# EASY_EDA_FILE_SCHEMATIC.net
KiCad netlist of a schematic drawn in EasyEDA
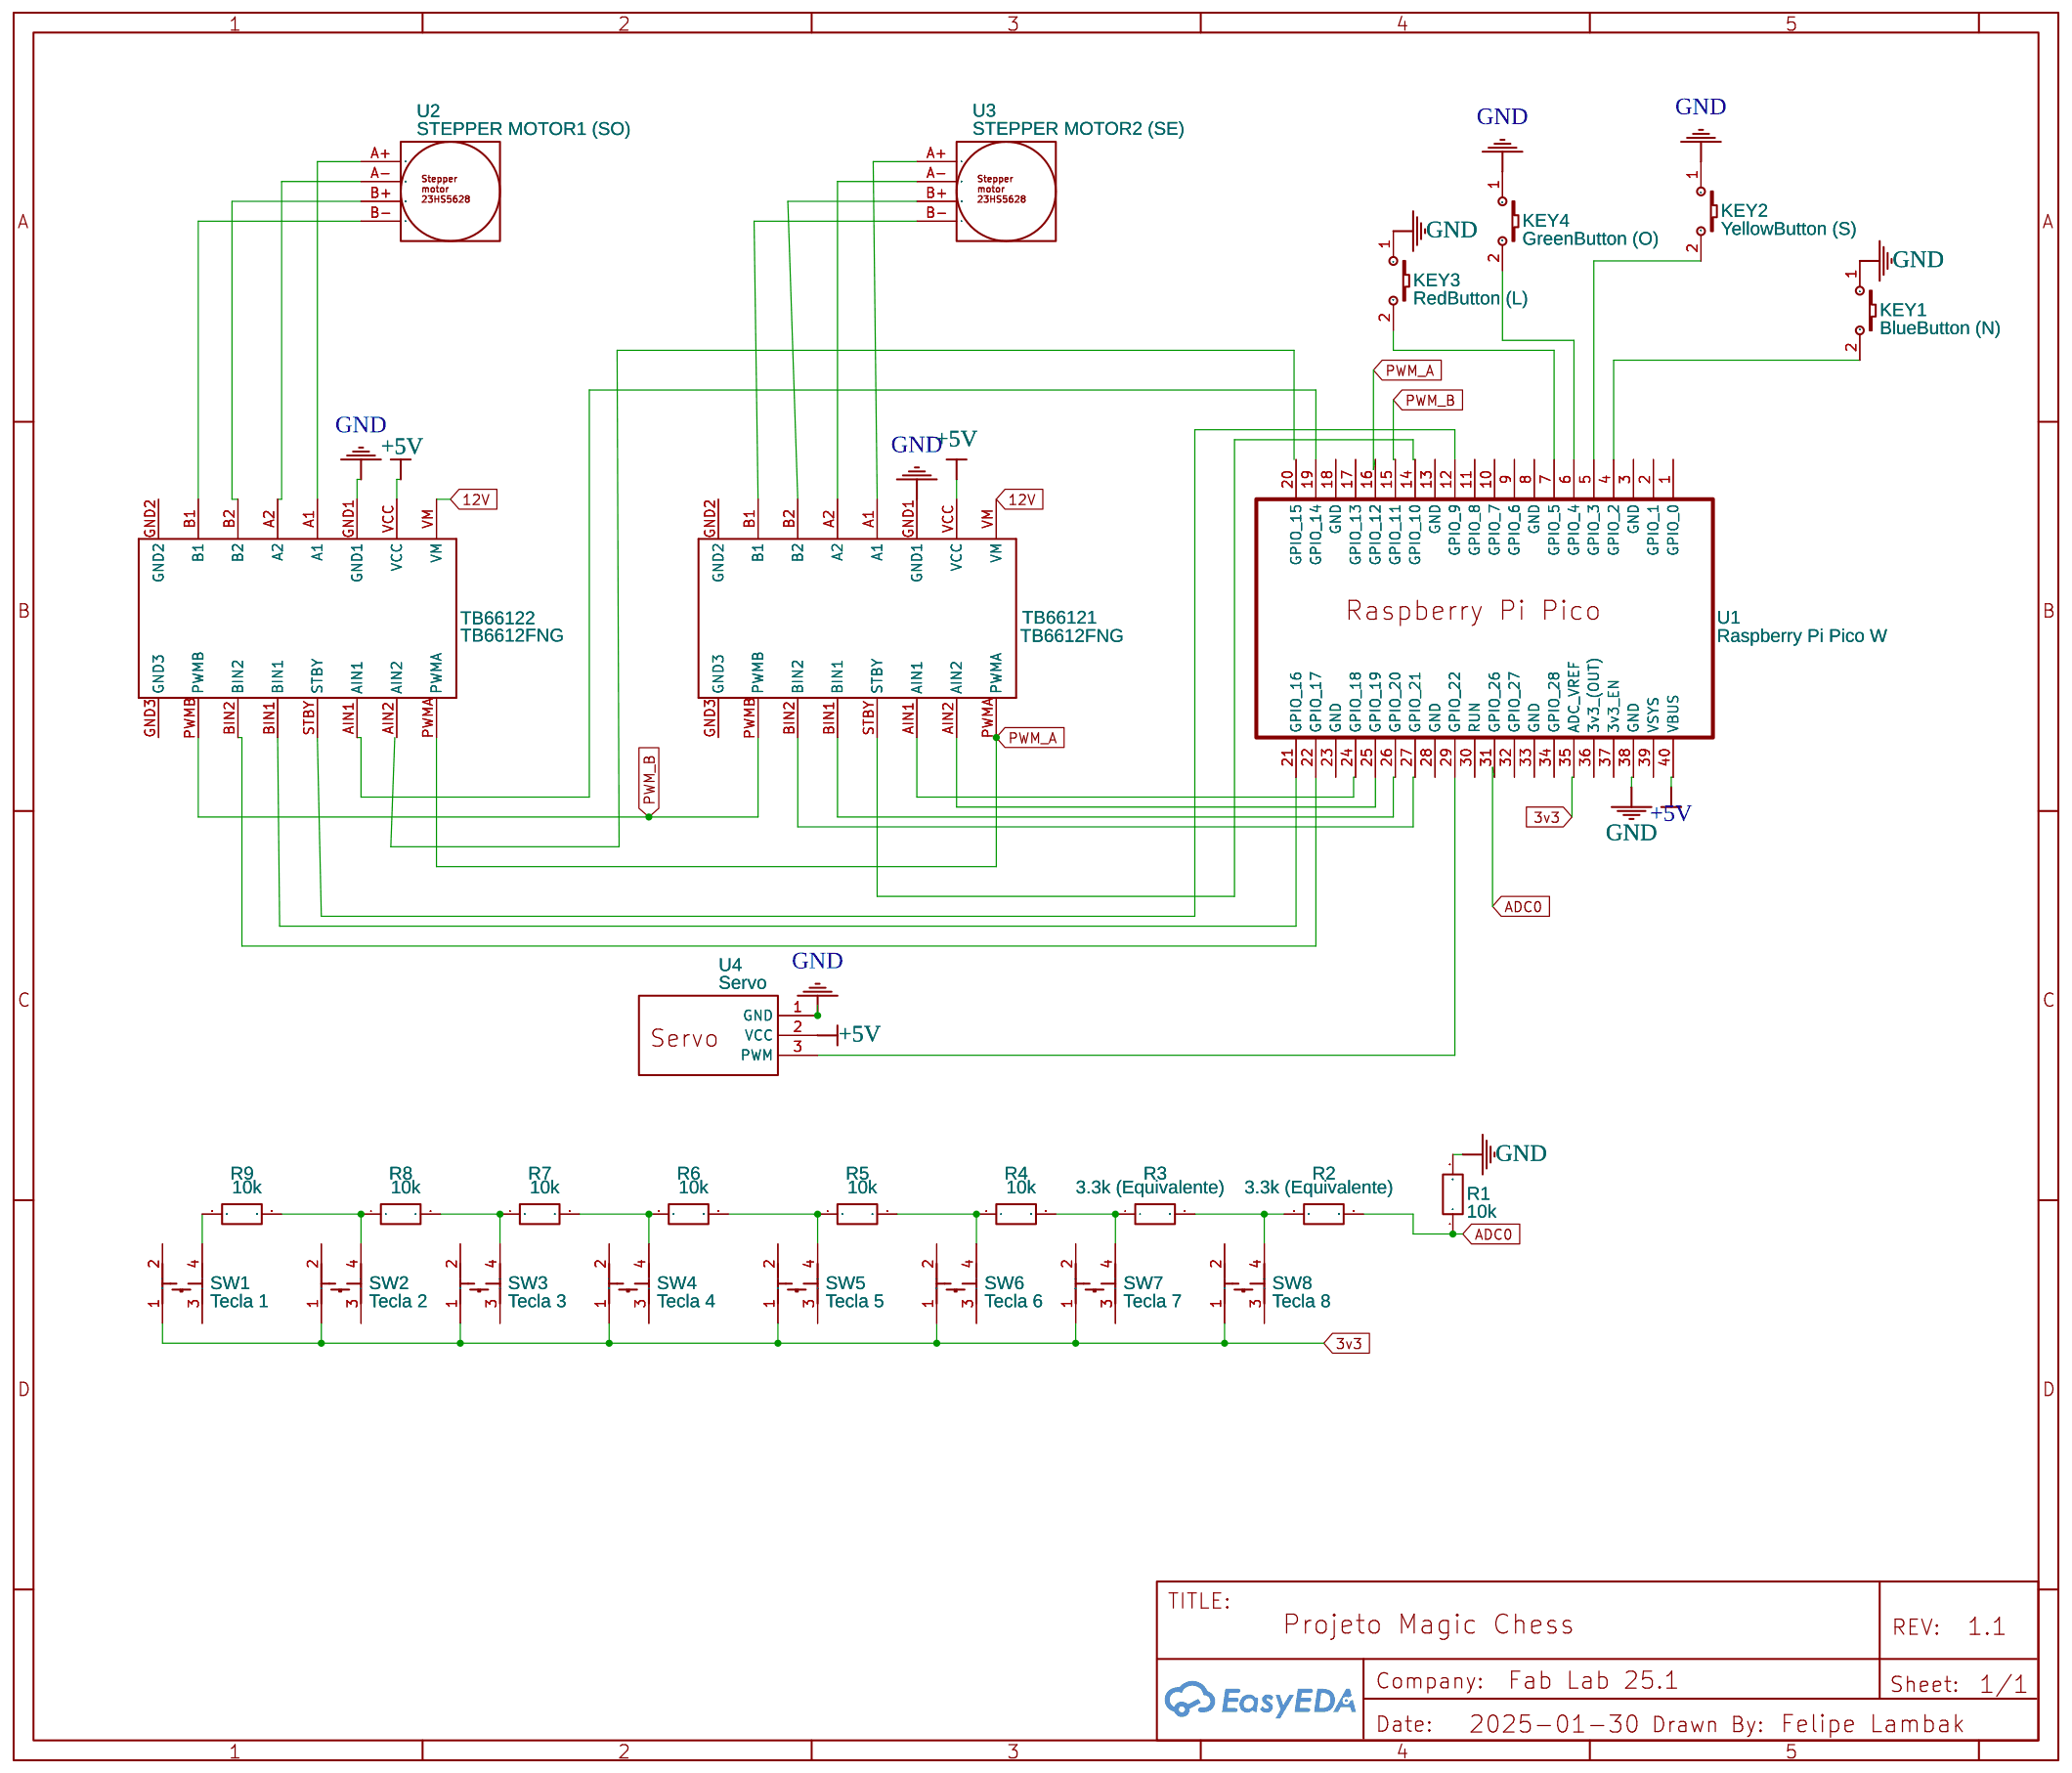
[diagram p0: schematic sheet]

(export (version "E")
  (design (tool "Eeschema 10.0.6"))
  (components
    (comp (ref "KEY1")
      (value "BlueButton (N)")
      (fields (field (name "Manufacturer Part") "K2-1107ST-A4SW-06"))
      (libsource (lib "") (part "K2-3.6×6.1_SMD"))
    )
    (comp (ref "KEY2")
      (value "YellowButton (S)")
      (fields (field (name "Manufacturer Part") "K2-1107ST-A4SW-06"))
      (libsource (lib "") (part "K2-3.6×6.1_SMD"))
    )
    (comp (ref "KEY3")
      (value "RedButton (L)")
      (fields (field (name "Manufacturer Part") "K2-1107ST-A4SW-06"))
      (libsource (lib "") (part "K2-3.6×6.1_SMD"))
    )
    (comp (ref "KEY4")
      (value "GreenButton (O)")
      (fields (field (name "Manufacturer Part") "K2-1107ST-A4SW-06"))
      (libsource (lib "") (part "K2-3.6×6.1_SMD"))
    )
    (comp (ref "R1") (value "10k") (libsource (lib "") (part "R_0603_EU_1")))
    (comp (ref "R2") (value "3.3k (Equivalente)") (libsource (lib "") (part "R_0603_EU")))
    (comp (ref "R3") (value "3.3k (Equivalente)") (libsource (lib "") (part "R_0603_EU")))
    (comp (ref "R4") (value "10k") (libsource (lib "") (part "R_0603_EU")))
    (comp (ref "R5") (value "10k") (libsource (lib "") (part "R_0603_EU")))
    (comp (ref "R6") (value "10k") (libsource (lib "") (part "R_0603_EU")))
    (comp (ref "R7") (value "10k") (libsource (lib "") (part "R_0603_EU")))
    (comp (ref "R8") (value "10k") (libsource (lib "") (part "R_0603_EU")))
    (comp (ref "R9") (value "10k") (libsource (lib "") (part "R_0603_EU")))
    (comp (ref "SW1")
      (value "Tecla 1")
      (fields (field (name "Manufacturer Part") "BUTTON-4X3X2.5"))
      (libsource (lib "") (part "BUTTON-4X3X2.5"))
    )
    (comp (ref "SW2")
      (value "Tecla 2")
      (fields (field (name "Manufacturer Part") "BUTTON-4X3X2.5"))
      (libsource (lib "") (part "BUTTON-4X3X2.5"))
    )
    (comp (ref "SW3")
      (value "Tecla 3")
      (fields (field (name "Manufacturer Part") "BUTTON-4X3X2.5"))
      (libsource (lib "") (part "BUTTON-4X3X2.5"))
    )
    (comp (ref "SW4")
      (value "Tecla 4")
      (fields (field (name "Manufacturer Part") "BUTTON-4X3X2.5"))
      (libsource (lib "") (part "BUTTON-4X3X2.5"))
    )
    (comp (ref "SW5")
      (value "Tecla 5")
      (fields (field (name "Manufacturer Part") "BUTTON-4X3X2.5"))
      (libsource (lib "") (part "BUTTON-4X3X2.5"))
    )
    (comp (ref "SW6")
      (value "Tecla 6")
      (fields (field (name "Manufacturer Part") "BUTTON-4X3X2.5"))
      (libsource (lib "") (part "BUTTON-4X3X2.5"))
    )
    (comp (ref "SW7")
      (value "Tecla 7")
      (fields (field (name "Manufacturer Part") "BUTTON-4X3X2.5"))
      (libsource (lib "") (part "BUTTON-4X3X2.5"))
    )
    (comp (ref "SW8")
      (value "Tecla 8")
      (fields (field (name "Manufacturer Part") "BUTTON-4X3X2.5"))
      (libsource (lib "") (part "BUTTON-4X3X2.5"))
    )
    (comp (ref "TB66121") (value "TB6612FNG") (libsource (lib "") (part "TB6612FNG")))
    (comp (ref "TB66122") (value "TB6612FNG") (libsource (lib "") (part "TB6612FNG")))
    (comp (ref "U1") (value "Raspberry Pi Pico W") (libsource (lib "") (part "Raspberry Pi Pico W")))
    (comp (ref "U2")
      (value "STEPPER MOTOR1 (SO)")
      (fields (field (name "Manufacturer Part") "MOTOR"))
      (libsource (lib "") (part "STEPPER MOTOR"))
    )
    (comp (ref "U3")
      (value "STEPPER MOTOR2 (SE)")
      (fields (field (name "Manufacturer Part") "MOTOR"))
      (libsource (lib "") (part "STEPPER MOTOR"))
    )
    (comp (ref "U4") (value "Servo") (libsource (lib "") (part "Servo")))
  )
  (nets
    (net (code "1") (name "+5V") (class "Default")
      (node (ref "TB66121") (pin "VCC") (pinfunction "VCC_VCC") (pintype "bidirectional"))
      (node (ref "TB66122") (pin "VCC") (pinfunction "VCC_VCC") (pintype "bidirectional"))
      (node (ref "U1") (pin "40") (pinfunction "VBUS_40") (pintype "unspecified"))
      (node (ref "U4") (pin "2") (pinfunction "VCC_2") (pintype "unspecified"))
    )
    (net (code "2") (name "3v3") (class "Default")
      (node (ref "SW1") (pin "1") (pinfunction "1_1") (pintype "unspecified"))
      (node (ref "SW2") (pin "1") (pinfunction "1_1") (pintype "unspecified"))
      (node (ref "SW3") (pin "1") (pinfunction "1_1") (pintype "unspecified"))
      (node (ref "SW4") (pin "1") (pinfunction "1_1") (pintype "unspecified"))
      (node (ref "SW5") (pin "1") (pinfunction "1_1") (pintype "unspecified"))
      (node (ref "SW6") (pin "1") (pinfunction "1_1") (pintype "unspecified"))
      (node (ref "SW7") (pin "1") (pinfunction "1_1") (pintype "unspecified"))
      (node (ref "SW8") (pin "1") (pinfunction "1_1") (pintype "unspecified"))
      (node (ref "U1") (pin "35") (pinfunction "ADC_VREF_35") (pintype "unspecified"))
    )
    (net (code "3") (name "12V") (class "Default")
      (node (ref "TB66121") (pin "VM") (pinfunction "VM_VM") (pintype "bidirectional"))
      (node (ref "TB66122") (pin "VM") (pinfunction "VM_VM") (pintype "bidirectional"))
    )
    (net (code "4") (name "ADC0") (class "Default")
      (node (ref "R1") (pin "1") (pinfunction "1_1") (pintype "unspecified"))
      (node (ref "R2") (pin "2") (pinfunction "2_2") (pintype "unspecified"))
      (node (ref "U1") (pin "31") (pinfunction "GPIO_26_31") (pintype "unspecified"))
    )
    (net (code "5") (name "GND") (class "Default")
      (node (ref "KEY1") (pin "1") (pinfunction "1_1") (pintype "unspecified"))
      (node (ref "KEY2") (pin "1") (pinfunction "1_1") (pintype "unspecified"))
      (node (ref "KEY3") (pin "1") (pinfunction "1_1") (pintype "unspecified"))
      (node (ref "KEY4") (pin "1") (pinfunction "1_1") (pintype "unspecified"))
      (node (ref "R1") (pin "2") (pinfunction "2_2") (pintype "unspecified"))
      (node (ref "TB66121") (pin "GND1") (pinfunction "GND1_GND1") (pintype "bidirectional"))
      (node (ref "TB66122") (pin "GND1") (pinfunction "GND1_GND1") (pintype "bidirectional"))
      (node (ref "U1") (pin "38") (pinfunction "GND_38") (pintype "unspecified"))
      (node (ref "U4") (pin "1") (pinfunction "GND_1") (pintype "unspecified"))
    )
    (net (code "6") (name "Net-(R2-Pad1)") (class "Default")
      (node (ref "R2") (pin "1") (pinfunction "1_1") (pintype "unspecified"))
      (node (ref "R3") (pin "2") (pinfunction "2_2") (pintype "unspecified"))
      (node (ref "SW8") (pin "4") (pinfunction "4_4") (pintype "unspecified"))
    )
    (net (code "7") (name "Net-(R3-Pad1)") (class "Default")
      (node (ref "R3") (pin "1") (pinfunction "1_1") (pintype "unspecified"))
      (node (ref "R4") (pin "2") (pinfunction "2_2") (pintype "unspecified"))
      (node (ref "SW7") (pin "4") (pinfunction "4_4") (pintype "unspecified"))
    )
    (net (code "8") (name "Net-(R4-Pad1)") (class "Default")
      (node (ref "R4") (pin "1") (pinfunction "1_1") (pintype "unspecified"))
      (node (ref "R5") (pin "2") (pinfunction "2_2") (pintype "unspecified"))
      (node (ref "SW6") (pin "4") (pinfunction "4_4") (pintype "unspecified"))
    )
    (net (code "9") (name "Net-(R5-Pad1)") (class "Default")
      (node (ref "R5") (pin "1") (pinfunction "1_1") (pintype "unspecified"))
      (node (ref "R6") (pin "2") (pinfunction "2_2") (pintype "unspecified"))
      (node (ref "SW5") (pin "4") (pinfunction "4_4") (pintype "unspecified"))
    )
    (net (code "10") (name "Net-(R6-Pad1)") (class "Default")
      (node (ref "R6") (pin "1") (pinfunction "1_1") (pintype "unspecified"))
      (node (ref "R7") (pin "2") (pinfunction "2_2") (pintype "unspecified"))
      (node (ref "SW4") (pin "4") (pinfunction "4_4") (pintype "unspecified"))
    )
    (net (code "11") (name "Net-(R7-Pad1)") (class "Default")
      (node (ref "R7") (pin "1") (pinfunction "1_1") (pintype "unspecified"))
      (node (ref "R8") (pin "2") (pinfunction "2_2") (pintype "unspecified"))
      (node (ref "SW3") (pin "4") (pinfunction "4_4") (pintype "unspecified"))
    )
    (net (code "12") (name "Net-(R8-Pad1)") (class "Default")
      (node (ref "R8") (pin "1") (pinfunction "1_1") (pintype "unspecified"))
      (node (ref "R9") (pin "2") (pinfunction "2_2") (pintype "unspecified"))
      (node (ref "SW2") (pin "4") (pinfunction "4_4") (pintype "unspecified"))
    )
    (net (code "13") (name "Net-(R9-Pad1)") (class "Default")
      (node (ref "R9") (pin "1") (pinfunction "1_1") (pintype "unspecified"))
      (node (ref "SW1") (pin "4") (pinfunction "4_4") (pintype "unspecified"))
    )
    (net (code "14") (name "Net-(U1-GPIO_2)") (class "Default")
      (node (ref "KEY1") (pin "2") (pinfunction "2_2") (pintype "unspecified"))
      (node (ref "U1") (pin "4") (pinfunction "GPIO_2_4") (pintype "unspecified"))
    )
    (net (code "15") (name "Net-(U1-GPIO_3)") (class "Default")
      (node (ref "KEY2") (pin "2") (pinfunction "2_2") (pintype "unspecified"))
      (node (ref "U1") (pin "5") (pinfunction "GPIO_3_5") (pintype "unspecified"))
    )
    (net (code "16") (name "Net-(U1-GPIO_4)") (class "Default")
      (node (ref "KEY4") (pin "2") (pinfunction "2_2") (pintype "unspecified"))
      (node (ref "U1") (pin "6") (pinfunction "GPIO_4_6") (pintype "unspecified"))
    )
    (net (code "17") (name "Net-(U1-GPIO_5)") (class "Default")
      (node (ref "KEY3") (pin "2") (pinfunction "2_2") (pintype "unspecified"))
      (node (ref "U1") (pin "7") (pinfunction "GPIO_5_7") (pintype "unspecified"))
    )
    (net (code "18") (name "Net-(U1-GPIO_9)") (class "Default")
      (node (ref "TB66122") (pin "STBY") (pinfunction "STBY_STBY") (pintype "bidirectional"))
      (node (ref "U1") (pin "12") (pinfunction "GPIO_9_12") (pintype "unspecified"))
    )
    (net (code "19") (name "Net-(U1-GPIO_10)") (class "Default")
      (node (ref "TB66121") (pin "STBY") (pinfunction "STBY_STBY") (pintype "bidirectional"))
      (node (ref "U1") (pin "14") (pinfunction "GPIO_10_14") (pintype "unspecified"))
    )
    (net (code "20") (name "Net-(U1-GPIO_14)") (class "Default")
      (node (ref "TB66122") (pin "AIN1") (pinfunction "AIN1_AIN1") (pintype "bidirectional"))
      (node (ref "U1") (pin "19") (pinfunction "GPIO_14_19") (pintype "unspecified"))
    )
    (net (code "21") (name "Net-(U1-GPIO_16)") (class "Default")
      (node (ref "TB66122") (pin "BIN1") (pinfunction "BIN1_BIN1") (pintype "bidirectional"))
      (node (ref "U1") (pin "21") (pinfunction "GPIO_16_21") (pintype "unspecified"))
    )
    (net (code "22") (name "Net-(U1-GPIO_17)") (class "Default")
      (node (ref "TB66122") (pin "BIN2") (pinfunction "BIN2_BIN2") (pintype "bidirectional"))
      (node (ref "U1") (pin "22") (pinfunction "GPIO_17_22") (pintype "unspecified"))
    )
    (net (code "23") (name "Net-(U1-GPIO_18)") (class "Default")
      (node (ref "TB66121") (pin "AIN1") (pinfunction "AIN1_AIN1") (pintype "bidirectional"))
      (node (ref "U1") (pin "24") (pinfunction "GPIO_18_24") (pintype "unspecified"))
    )
    (net (code "24") (name "Net-(U1-GPIO_19)") (class "Default")
      (node (ref "TB66121") (pin "AIN2") (pinfunction "AIN2_AIN2") (pintype "bidirectional"))
      (node (ref "U1") (pin "25") (pinfunction "GPIO_19_25") (pintype "unspecified"))
    )
    (net (code "25") (name "Net-(U1-GPIO_20)") (class "Default")
      (node (ref "TB66121") (pin "BIN1") (pinfunction "BIN1_BIN1") (pintype "bidirectional"))
      (node (ref "U1") (pin "26") (pinfunction "GPIO_20_26") (pintype "unspecified"))
    )
    (net (code "26") (name "Net-(U1-GPIO_21)") (class "Default")
      (node (ref "TB66121") (pin "BIN2") (pinfunction "BIN2_BIN2") (pintype "bidirectional"))
      (node (ref "U1") (pin "27") (pinfunction "GPIO_21_27") (pintype "unspecified"))
    )
    (net (code "27") (name "Net-(U1-GPIO_22)") (class "Default")
      (node (ref "U1") (pin "29") (pinfunction "GPIO_22_29") (pintype "unspecified"))
      (node (ref "U4") (pin "3") (pinfunction "PWM_3") (pintype "unspecified"))
    )
    (net (code "28") (name "Net-(U2-1)") (class "Default")
      (node (ref "TB66122") (pin "A1") (pinfunction "A1_A1") (pintype "bidirectional"))
      (node (ref "U2") (pin "A+") (pinfunction "1_A+") (pintype "unspecified"))
    )
    (net (code "29") (name "Net-(U2-2)") (class "Default")
      (node (ref "TB66122") (pin "A2") (pinfunction "A2_A2") (pintype "bidirectional"))
      (node (ref "U2") (pin "A-") (pinfunction "2_A-") (pintype "unspecified"))
    )
    (net (code "30") (name "Net-(U2-3)") (class "Default")
      (node (ref "TB66122") (pin "B2") (pinfunction "B2_B2") (pintype "bidirectional"))
      (node (ref "U2") (pin "B+") (pinfunction "3_B+") (pintype "unspecified"))
    )
    (net (code "31") (name "Net-(U2-4)") (class "Default")
      (node (ref "TB66122") (pin "B1") (pinfunction "B1_B1") (pintype "bidirectional"))
      (node (ref "U2") (pin "B-") (pinfunction "4_B-") (pintype "unspecified"))
    )
    (net (code "32") (name "Net-(U3-1)") (class "Default")
      (node (ref "TB66121") (pin "A1") (pinfunction "A1_A1") (pintype "bidirectional"))
      (node (ref "U3") (pin "A+") (pinfunction "1_A+") (pintype "unspecified"))
    )
    (net (code "33") (name "Net-(U3-2)") (class "Default")
      (node (ref "TB66121") (pin "A2") (pinfunction "A2_A2") (pintype "bidirectional"))
      (node (ref "U3") (pin "A-") (pinfunction "2_A-") (pintype "unspecified"))
    )
    (net (code "34") (name "Net-(U3-3)") (class "Default")
      (node (ref "TB66121") (pin "B2") (pinfunction "B2_B2") (pintype "bidirectional"))
      (node (ref "U3") (pin "B+") (pinfunction "3_B+") (pintype "unspecified"))
    )
    (net (code "35") (name "Net-(U3-4)") (class "Default")
      (node (ref "TB66121") (pin "B1") (pinfunction "B1_B1") (pintype "bidirectional"))
      (node (ref "U3") (pin "B-") (pinfunction "4_B-") (pintype "unspecified"))
    )
    (net (code "36") (name "PWM_A") (class "Default")
      (node (ref "TB66121") (pin "PWMA") (pinfunction "PWMA_PWMA") (pintype "bidirectional"))
      (node (ref "TB66122") (pin "PWMA") (pinfunction "PWMA_PWMA") (pintype "bidirectional"))
      (node (ref "U1") (pin "16") (pinfunction "GPIO_12_16") (pintype "unspecified"))
    )
    (net (code "37") (name "PWM_B") (class "Default")
      (node (ref "TB66121") (pin "PWMB") (pinfunction "PWMB_PWMB") (pintype "bidirectional"))
      (node (ref "TB66122") (pin "PWMB") (pinfunction "PWMB_PWMB") (pintype "bidirectional"))
      (node (ref "U1") (pin "15") (pinfunction "GPIO_11_15") (pintype "unspecified"))
    )
    (net (code "38") (name "unconnected-(SW1-Pad2)") (class "Default")
      (node (ref "SW1") (pin "2") (pinfunction "2_2") (pintype "unspecified"))
    )
    (net (code "39") (name "unconnected-(SW1-Pad3)") (class "Default")
      (node (ref "SW1") (pin "3") (pinfunction "3_3") (pintype "unspecified"))
    )
    (net (code "40") (name "unconnected-(SW2-Pad2)") (class "Default")
      (node (ref "SW2") (pin "2") (pinfunction "2_2") (pintype "unspecified"))
    )
    (net (code "41") (name "unconnected-(SW2-Pad3)") (class "Default")
      (node (ref "SW2") (pin "3") (pinfunction "3_3") (pintype "unspecified"))
    )
    (net (code "42") (name "unconnected-(SW3-Pad2)") (class "Default")
      (node (ref "SW3") (pin "2") (pinfunction "2_2") (pintype "unspecified"))
    )
    (net (code "43") (name "unconnected-(SW3-Pad3)") (class "Default")
      (node (ref "SW3") (pin "3") (pinfunction "3_3") (pintype "unspecified"))
    )
    (net (code "44") (name "unconnected-(SW4-Pad2)") (class "Default")
      (node (ref "SW4") (pin "2") (pinfunction "2_2") (pintype "unspecified"))
    )
    (net (code "45") (name "unconnected-(SW4-Pad3)") (class "Default")
      (node (ref "SW4") (pin "3") (pinfunction "3_3") (pintype "unspecified"))
    )
    (net (code "46") (name "unconnected-(SW5-Pad2)") (class "Default")
      (node (ref "SW5") (pin "2") (pinfunction "2_2") (pintype "unspecified"))
    )
    (net (code "47") (name "unconnected-(SW5-Pad3)") (class "Default")
      (node (ref "SW5") (pin "3") (pinfunction "3_3") (pintype "unspecified"))
    )
    (net (code "48") (name "unconnected-(SW6-Pad2)") (class "Default")
      (node (ref "SW6") (pin "2") (pinfunction "2_2") (pintype "unspecified"))
    )
    (net (code "49") (name "unconnected-(SW6-Pad3)") (class "Default")
      (node (ref "SW6") (pin "3") (pinfunction "3_3") (pintype "unspecified"))
    )
    (net (code "50") (name "unconnected-(SW7-Pad2)") (class "Default")
      (node (ref "SW7") (pin "2") (pinfunction "2_2") (pintype "unspecified"))
    )
    (net (code "51") (name "unconnected-(SW7-Pad3)") (class "Default")
      (node (ref "SW7") (pin "3") (pinfunction "3_3") (pintype "unspecified"))
    )
    (net (code "52") (name "unconnected-(SW8-Pad2)") (class "Default")
      (node (ref "SW8") (pin "2") (pinfunction "2_2") (pintype "unspecified"))
    )
    (net (code "53") (name "unconnected-(SW8-Pad3)") (class "Default")
      (node (ref "SW8") (pin "3") (pinfunction "3_3") (pintype "unspecified"))
    )
    (net (code "54") (name "unconnected-(TB66121-PadGND2)") (class "Default")
      (node (ref "TB66121") (pin "GND2") (pinfunction "GND2_GND2") (pintype "bidirectional"))
    )
    (net (code "55") (name "unconnected-(TB66121-PadGND3)") (class "Default")
      (node (ref "TB66121") (pin "GND3") (pinfunction "GND3_GND3") (pintype "bidirectional"))
    )
    (net (code "56") (name "unconnected-(TB66122-PadAIN2)") (class "Default")
      (node (ref "TB66122") (pin "AIN2") (pinfunction "AIN2_AIN2") (pintype "bidirectional"))
    )
    (net (code "57") (name "unconnected-(TB66122-PadGND2)") (class "Default")
      (node (ref "TB66122") (pin "GND2") (pinfunction "GND2_GND2") (pintype "bidirectional"))
    )
    (net (code "58") (name "unconnected-(TB66122-PadGND3)") (class "Default")
      (node (ref "TB66122") (pin "GND3") (pinfunction "GND3_GND3") (pintype "bidirectional"))
    )
    (net (code "59") (name "unconnected-(U1-3v3_(OUT)-Pad36)") (class "Default")
      (node (ref "U1") (pin "36") (pinfunction "3v3_(OUT)_36") (pintype "unspecified"))
    )
    (net (code "60") (name "unconnected-(U1-3v3_EN-Pad37)") (class "Default")
      (node (ref "U1") (pin "37") (pinfunction "3v3_EN_37") (pintype "unspecified"))
    )
    (net (code "61") (name "unconnected-(U1-GND-Pad3)") (class "Default")
      (node (ref "U1") (pin "3") (pinfunction "GND_3") (pintype "unspecified"))
    )
    (net (code "62") (name "unconnected-(U1-GND-Pad8)") (class "Default")
      (node (ref "U1") (pin "8") (pinfunction "GND_8") (pintype "unspecified"))
    )
    (net (code "63") (name "unconnected-(U1-GND-Pad13)") (class "Default")
      (node (ref "U1") (pin "13") (pinfunction "GND_13") (pintype "unspecified"))
    )
    (net (code "64") (name "unconnected-(U1-GND-Pad18)") (class "Default")
      (node (ref "U1") (pin "18") (pinfunction "GND_18") (pintype "unspecified"))
    )
    (net (code "65") (name "unconnected-(U1-GND-Pad23)") (class "Default")
      (node (ref "U1") (pin "23") (pinfunction "GND_23") (pintype "unspecified"))
    )
    (net (code "66") (name "unconnected-(U1-GND-Pad28)") (class "Default")
      (node (ref "U1") (pin "28") (pinfunction "GND_28") (pintype "unspecified"))
    )
    (net (code "67") (name "unconnected-(U1-GND-Pad33)") (class "Default")
      (node (ref "U1") (pin "33") (pinfunction "GND_33") (pintype "unspecified"))
    )
    (net (code "68") (name "unconnected-(U1-GPIO_0-Pad1)") (class "Default")
      (node (ref "U1") (pin "1") (pinfunction "GPIO_0_1") (pintype "unspecified"))
    )
    (net (code "69") (name "unconnected-(U1-GPIO_1-Pad2)") (class "Default")
      (node (ref "U1") (pin "2") (pinfunction "GPIO_1_2") (pintype "unspecified"))
    )
    (net (code "70") (name "unconnected-(U1-GPIO_6-Pad9)") (class "Default")
      (node (ref "U1") (pin "9") (pinfunction "GPIO_6_9") (pintype "unspecified"))
    )
    (net (code "71") (name "unconnected-(U1-GPIO_7-Pad10)") (class "Default")
      (node (ref "U1") (pin "10") (pinfunction "GPIO_7_10") (pintype "unspecified"))
    )
    (net (code "72") (name "unconnected-(U1-GPIO_8-Pad11)") (class "Default")
      (node (ref "U1") (pin "11") (pinfunction "GPIO_8_11") (pintype "unspecified"))
    )
    (net (code "73") (name "unconnected-(U1-GPIO_13-Pad17)") (class "Default")
      (node (ref "U1") (pin "17") (pinfunction "GPIO_13_17") (pintype "unspecified"))
    )
    (net (code "74") (name "unconnected-(U1-GPIO_15-Pad20)") (class "Default")
      (node (ref "U1") (pin "20") (pinfunction "GPIO_15_20") (pintype "unspecified"))
    )
    (net (code "75") (name "unconnected-(U1-GPIO_27-Pad32)") (class "Default")
      (node (ref "U1") (pin "32") (pinfunction "GPIO_27_32") (pintype "unspecified"))
    )
    (net (code "76") (name "unconnected-(U1-GPIO_28-Pad34)") (class "Default")
      (node (ref "U1") (pin "34") (pinfunction "GPIO_28_34") (pintype "unspecified"))
    )
    (net (code "77") (name "unconnected-(U1-RUN-Pad30)") (class "Default")
      (node (ref "U1") (pin "30") (pinfunction "RUN_30") (pintype "unspecified"))
    )
    (net (code "78") (name "unconnected-(U1-VSYS-Pad39)") (class "Default")
      (node (ref "U1") (pin "39") (pinfunction "VSYS_39") (pintype "unspecified"))
    )
  )
)
